# Amplificador.net
KiCad netlist of a schematic drawn in EAGLE
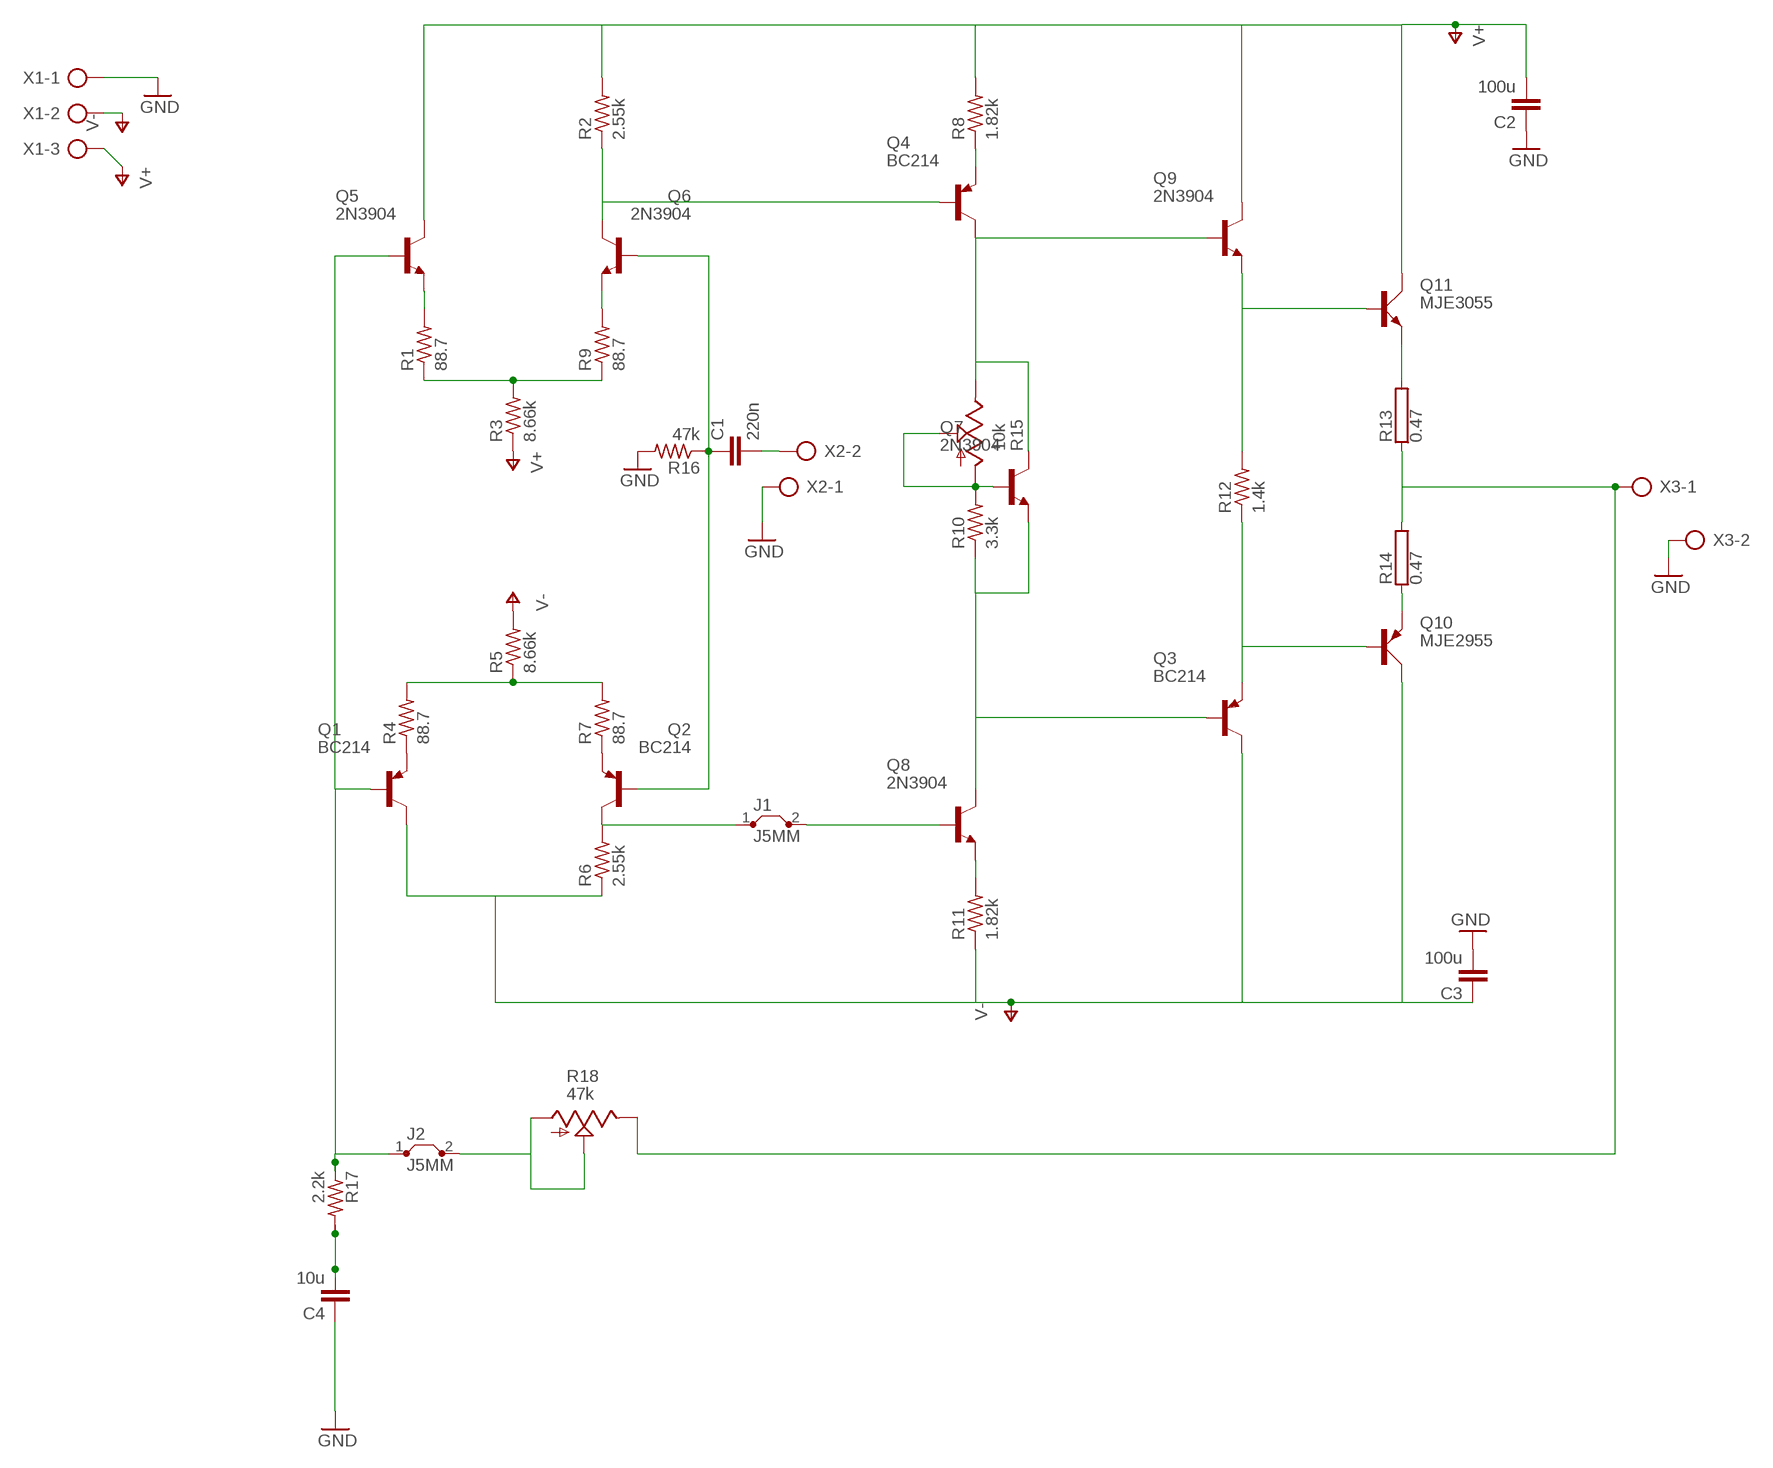
[diagram p0: schematic, sheet 1]

(export (version "E")
  (design (tool "Eeschema 10.0.6"))
  (components
    (comp (ref "C1")
      (value "220n")
      (footprint "eagle-import:C5B2.5")
      (libsource (lib "eagle-import") (part "C5/2.5"))
    )
    (comp (ref "C2")
      (value "100u")
      (footprint "eagle-import:C5B2.5")
      (libsource (lib "eagle-import") (part "C5/2.5"))
    )
    (comp (ref "C3")
      (value "100u")
      (footprint "eagle-import:C5B2.5")
      (libsource (lib "eagle-import") (part "C5/2.5"))
    )
    (comp (ref "C4")
      (value "10u")
      (footprint "eagle-import:C5B2.5")
      (libsource (lib "eagle-import") (part "C5/2.5"))
    )
    (comp (ref "J1")
      (value "J5MM")
      (footprint "eagle-import:05")
      (libsource (lib "eagle-import") (part "J5MM"))
    )
    (comp (ref "J2")
      (value "J5MM")
      (footprint "eagle-import:05")
      (libsource (lib "eagle-import") (part "J5MM"))
    )
    (comp (ref "Q1")
      (value "BC214")
      (footprint "eagle-import:TO92")
      (libsource (lib "eagle-import") (part "BC214"))
    )
    (comp (ref "Q2")
      (value "BC214")
      (footprint "eagle-import:TO92")
      (libsource (lib "eagle-import") (part "BC214"))
    )
    (comp (ref "Q3")
      (value "BC214")
      (footprint "eagle-import:TO92")
      (libsource (lib "eagle-import") (part "BC214"))
    )
    (comp (ref "Q4")
      (value "BC214")
      (footprint "eagle-import:TO92")
      (libsource (lib "eagle-import") (part "BC214"))
    )
    (comp (ref "Q5")
      (value "2N3904")
      (footprint "eagle-import:TO92")
      (libsource (lib "eagle-import") (part "2N3904"))
    )
    (comp (ref "Q6")
      (value "2N3904")
      (footprint "eagle-import:TO92")
      (libsource (lib "eagle-import") (part "2N3904"))
    )
    (comp (ref "Q7")
      (value "2N3904")
      (footprint "eagle-import:TO92")
      (libsource (lib "eagle-import") (part "2N3904"))
    )
    (comp (ref "Q8")
      (value "2N3904")
      (footprint "eagle-import:TO92")
      (libsource (lib "eagle-import") (part "2N3904"))
    )
    (comp (ref "Q9")
      (value "2N3904")
      (footprint "eagle-import:TO92")
      (libsource (lib "eagle-import") (part "2N3904"))
    )
    (comp (ref "Q10")
      (value "MJE2955")
      (footprint "eagle-import:TO220AV")
      (libsource (lib "eagle-import") (part "MJE2955"))
    )
    (comp (ref "Q11")
      (value "MJE3055")
      (footprint "eagle-import:TO220AV")
      (libsource (lib "eagle-import") (part "MJE3055"))
    )
    (comp (ref "R1")
      (value "88.7")
      (footprint "eagle-import:0207_10")
      (libsource (lib "eagle-import") (part "R-US_0207/10"))
    )
    (comp (ref "R2")
      (value "2.55k")
      (footprint "eagle-import:0207_10")
      (libsource (lib "eagle-import") (part "R-US_0207/10"))
    )
    (comp (ref "R3")
      (value "8.66k")
      (footprint "eagle-import:0207_10")
      (libsource (lib "eagle-import") (part "R-US_0207/10"))
    )
    (comp (ref "R4")
      (value "88.7")
      (footprint "eagle-import:0207_10")
      (libsource (lib "eagle-import") (part "R-US_0207/10"))
    )
    (comp (ref "R5")
      (value "8.66k")
      (footprint "eagle-import:0207_10")
      (libsource (lib "eagle-import") (part "R-US_0207/10"))
    )
    (comp (ref "R6")
      (value "2.55k")
      (footprint "eagle-import:0207_10")
      (libsource (lib "eagle-import") (part "R-US_0207/10"))
    )
    (comp (ref "R7")
      (value "88.7")
      (footprint "eagle-import:0207_10")
      (libsource (lib "eagle-import") (part "R-US_0207/10"))
    )
    (comp (ref "R8")
      (value "1.82k")
      (footprint "eagle-import:0207_10")
      (libsource (lib "eagle-import") (part "R-US_0207/10"))
    )
    (comp (ref "R9")
      (value "88.7")
      (footprint "eagle-import:0207_10")
      (libsource (lib "eagle-import") (part "R-US_0207/10"))
    )
    (comp (ref "R10")
      (value "3.3k")
      (footprint "eagle-import:0207_10")
      (libsource (lib "eagle-import") (part "R-US_0207/10"))
    )
    (comp (ref "R11")
      (value "1.82k")
      (footprint "eagle-import:0207_10")
      (libsource (lib "eagle-import") (part "R-US_0207/10"))
    )
    (comp (ref "R12")
      (value "1.4k")
      (footprint "eagle-import:0207_10")
      (libsource (lib "eagle-import") (part "R-US_0207/10"))
    )
    (comp (ref "R13")
      (value "0.47")
      (footprint "eagle-import:CA4055")
      (libsource (lib "eagle-import") (part "RCA4055"))
    )
    (comp (ref "R14")
      (value "0.47")
      (footprint "eagle-import:CA4055")
      (libsource (lib "eagle-import") (part "RCA4055"))
    )
    (comp (ref "R15")
      (value "10k")
      (footprint "eagle-import:CA6V")
      (libsource (lib "eagle-import") (part "TRIM_US-CA6V"))
    )
    (comp (ref "R16")
      (value "47k")
      (footprint "eagle-import:0207_10")
      (libsource (lib "eagle-import") (part "R-US_0207/10"))
    )
    (comp (ref "R17")
      (value "2.2k")
      (footprint "eagle-import:0207_10")
      (libsource (lib "eagle-import") (part "R-US_0207/10"))
    )
    (comp (ref "R18")
      (value "47k")
      (footprint "eagle-import:CA6H")
      (libsource (lib "eagle-import") (part "TRIM_US-CA6H"))
    )
    (comp (ref "X1")
      (value "AK500/3-H")
      (footprint "eagle-import:AK500_3-H")
      (libsource (lib "eagle-import") (part "AK500/3-H"))
    )
    (comp (ref "X2")
      (value "AK500/2-H")
      (footprint "eagle-import:AK500_2-H")
      (libsource (lib "eagle-import") (part "AK500/2-H"))
    )
    (comp (ref "X3")
      (value "AK500/2-H")
      (footprint "eagle-import:AK500_2-H")
      (libsource (lib "eagle-import") (part "AK500/2-H"))
    )
  )
  (nets
    (net (code "1") (name "GND") (class "Default")
      (node (ref "C2") (pin "1") (pinfunction "1_1") (pintype "passive"))
      (node (ref "C3") (pin "2") (pinfunction "2_2") (pintype "passive"))
      (node (ref "C4") (pin "1") (pinfunction "1_1") (pintype "passive"))
      (node (ref "R16") (pin "2") (pinfunction "2_2") (pintype "passive"))
      (node (ref "X1") (pin "1") (pinfunction "KL_1") (pintype "passive"))
      (node (ref "X2") (pin "1") (pinfunction "KL_1") (pintype "passive"))
      (node (ref "X3") (pin "2") (pinfunction "KL_2") (pintype "passive"))
    )
    (net (code "2") (name "Net-(C4-Pad2)") (class "Default")
      (node (ref "C4") (pin "2") (pinfunction "2_2") (pintype "passive"))
      (node (ref "R17") (pin "2") (pinfunction "2_2") (pintype "passive"))
    )
    (net (code "3") (name "Net-(J2-Pad2)") (class "Default")
      (node (ref "J2") (pin "2") (pinfunction "2_2") (pintype "passive"))
      (node (ref "R18") (pin "A") (pinfunction "A_A") (pintype "passive"))
      (node (ref "R18") (pin "S") (pinfunction "S_S") (pintype "passive"))
    )
    (net (code "4") (name "Net-(Q1-B)") (class "Default")
      (node (ref "J2") (pin "1") (pinfunction "1_1") (pintype "passive"))
      (node (ref "Q1") (pin "2") (pinfunction "B_2") (pintype "passive"))
      (node (ref "Q5") (pin "2") (pinfunction "B_2") (pintype "passive"))
      (node (ref "R17") (pin "1") (pinfunction "1_1") (pintype "passive"))
    )
    (net (code "5") (name "Net-(Q1-E)") (class "Default")
      (node (ref "Q1") (pin "1") (pinfunction "E_1") (pintype "passive"))
      (node (ref "R4") (pin "1") (pinfunction "1_1") (pintype "passive"))
    )
    (net (code "6") (name "Net-(Q2-B)") (class "Default")
      (node (ref "C1") (pin "1") (pinfunction "1_1") (pintype "passive"))
      (node (ref "Q2") (pin "2") (pinfunction "B_2") (pintype "passive"))
      (node (ref "Q6") (pin "2") (pinfunction "B_2") (pintype "passive"))
      (node (ref "R16") (pin "1") (pinfunction "1_1") (pintype "passive"))
    )
    (net (code "7") (name "Net-(Q2-C)") (class "Default")
      (node (ref "J1") (pin "1") (pinfunction "1_1") (pintype "passive"))
      (node (ref "Q2") (pin "3") (pinfunction "C_3") (pintype "passive"))
      (node (ref "R6") (pin "2") (pinfunction "2_2") (pintype "passive"))
    )
    (net (code "8") (name "Net-(Q2-E)") (class "Default")
      (node (ref "Q2") (pin "1") (pinfunction "E_1") (pintype "passive"))
      (node (ref "R7") (pin "1") (pinfunction "1_1") (pintype "passive"))
    )
    (net (code "9") (name "Net-(Q3-B)") (class "Default")
      (node (ref "Q3") (pin "2") (pinfunction "B_2") (pintype "passive"))
      (node (ref "Q7") (pin "3") (pinfunction "E_3") (pintype "passive"))
      (node (ref "Q8") (pin "1") (pinfunction "C_1") (pintype "passive"))
      (node (ref "R10") (pin "1") (pinfunction "1_1") (pintype "passive"))
    )
    (net (code "10") (name "Net-(Q3-E)") (class "Default")
      (node (ref "Q10") (pin "B") (pinfunction "B_B") (pintype "passive"))
      (node (ref "Q3") (pin "1") (pinfunction "E_1") (pintype "passive"))
      (node (ref "R12") (pin "1") (pinfunction "1_1") (pintype "passive"))
    )
    (net (code "11") (name "Net-(Q4-B)") (class "Default")
      (node (ref "Q4") (pin "2") (pinfunction "B_2") (pintype "passive"))
      (node (ref "Q6") (pin "1") (pinfunction "C_1") (pintype "passive"))
      (node (ref "R2") (pin "1") (pinfunction "1_1") (pintype "passive"))
    )
    (net (code "12") (name "Net-(Q4-C)") (class "Default")
      (node (ref "Q4") (pin "3") (pinfunction "C_3") (pintype "passive"))
      (node (ref "Q7") (pin "1") (pinfunction "C_1") (pintype "passive"))
      (node (ref "Q9") (pin "2") (pinfunction "B_2") (pintype "passive"))
      (node (ref "R15") (pin "E") (pinfunction "E_E") (pintype "passive"))
    )
    (net (code "13") (name "Net-(Q4-E)") (class "Default")
      (node (ref "Q4") (pin "1") (pinfunction "E_1") (pintype "passive"))
      (node (ref "R8") (pin "1") (pinfunction "1_1") (pintype "passive"))
    )
    (net (code "14") (name "Net-(Q5-E)") (class "Default")
      (node (ref "Q5") (pin "3") (pinfunction "E_3") (pintype "passive"))
      (node (ref "R1") (pin "2") (pinfunction "2_2") (pintype "passive"))
    )
    (net (code "15") (name "Net-(Q6-E)") (class "Default")
      (node (ref "Q6") (pin "3") (pinfunction "E_3") (pintype "passive"))
      (node (ref "R9") (pin "2") (pinfunction "2_2") (pintype "passive"))
    )
    (net (code "16") (name "Net-(Q7-B)") (class "Default")
      (node (ref "Q7") (pin "2") (pinfunction "B_2") (pintype "passive"))
      (node (ref "R10") (pin "2") (pinfunction "2_2") (pintype "passive"))
      (node (ref "R15") (pin "A") (pinfunction "A_A") (pintype "passive"))
      (node (ref "R15") (pin "S") (pinfunction "S_S") (pintype "passive"))
    )
    (net (code "17") (name "Net-(Q8-B)") (class "Default")
      (node (ref "J1") (pin "2") (pinfunction "2_2") (pintype "passive"))
      (node (ref "Q8") (pin "2") (pinfunction "B_2") (pintype "passive"))
    )
    (net (code "18") (name "Net-(Q8-E)") (class "Default")
      (node (ref "Q8") (pin "3") (pinfunction "E_3") (pintype "passive"))
      (node (ref "R11") (pin "2") (pinfunction "2_2") (pintype "passive"))
    )
    (net (code "19") (name "Net-(Q9-E)") (class "Default")
      (node (ref "Q11") (pin "B") (pinfunction "B_B") (pintype "passive"))
      (node (ref "Q9") (pin "3") (pinfunction "E_3") (pintype "passive"))
      (node (ref "R12") (pin "2") (pinfunction "2_2") (pintype "passive"))
    )
    (net (code "20") (name "Net-(Q10-PadE)") (class "Default")
      (node (ref "Q10") (pin "E") (pinfunction "E_E") (pintype "passive"))
      (node (ref "R14") (pin "1") (pinfunction "1_1") (pintype "passive"))
    )
    (net (code "21") (name "Net-(Q11-PadE)") (class "Default")
      (node (ref "Q11") (pin "E") (pinfunction "E_E") (pintype "passive"))
      (node (ref "R13") (pin "2") (pinfunction "2_2") (pintype "passive"))
    )
    (net (code "22") (name "Net-(R1-Pad1)") (class "Default")
      (node (ref "R1") (pin "1") (pinfunction "1_1") (pintype "passive"))
      (node (ref "R3") (pin "2") (pinfunction "2_2") (pintype "passive"))
      (node (ref "R9") (pin "1") (pinfunction "1_1") (pintype "passive"))
    )
    (net (code "23") (name "Net-(R4-Pad2)") (class "Default")
      (node (ref "R4") (pin "2") (pinfunction "2_2") (pintype "passive"))
      (node (ref "R5") (pin "1") (pinfunction "1_1") (pintype "passive"))
      (node (ref "R7") (pin "2") (pinfunction "2_2") (pintype "passive"))
    )
    (net (code "24") (name "Net-(X2B-KL)") (class "Default")
      (node (ref "C1") (pin "2") (pinfunction "2_2") (pintype "passive"))
      (node (ref "X2") (pin "2") (pinfunction "KL_2") (pintype "passive"))
    )
    (net (code "25") (name "Net-(X3A-KL)") (class "Default")
      (node (ref "R13") (pin "1") (pinfunction "1_1") (pintype "passive"))
      (node (ref "R14") (pin "2") (pinfunction "2_2") (pintype "passive"))
      (node (ref "R18") (pin "E") (pinfunction "E_E") (pintype "passive"))
      (node (ref "X3") (pin "1") (pinfunction "KL_1") (pintype "passive"))
    )
    (net (code "26") (name "V+") (class "Default")
      (node (ref "C2") (pin "2") (pinfunction "2_2") (pintype "passive"))
      (node (ref "Q11") (pin "C") (pinfunction "C_C") (pintype "passive"))
      (node (ref "Q5") (pin "1") (pinfunction "C_1") (pintype "passive"))
      (node (ref "Q9") (pin "1") (pinfunction "C_1") (pintype "passive"))
      (node (ref "R2") (pin "2") (pinfunction "2_2") (pintype "passive"))
      (node (ref "R3") (pin "1") (pinfunction "1_1") (pintype "passive"))
      (node (ref "R8") (pin "2") (pinfunction "2_2") (pintype "passive"))
      (node (ref "X1") (pin "3") (pinfunction "KL_3") (pintype "passive"))
    )
    (net (code "27") (name "V-") (class "Default")
      (node (ref "C3") (pin "1") (pinfunction "1_1") (pintype "passive"))
      (node (ref "Q1") (pin "3") (pinfunction "C_3") (pintype "passive"))
      (node (ref "Q10") (pin "C") (pinfunction "C_C") (pintype "passive"))
      (node (ref "Q3") (pin "3") (pinfunction "C_3") (pintype "passive"))
      (node (ref "R11") (pin "1") (pinfunction "1_1") (pintype "passive"))
      (node (ref "R5") (pin "2") (pinfunction "2_2") (pintype "passive"))
      (node (ref "R6") (pin "1") (pinfunction "1_1") (pintype "passive"))
      (node (ref "X1") (pin "2") (pinfunction "KL_2") (pintype "passive"))
    )
  )
)
